# AT_long_bus.net
KiCad netlist of a schematic drawn in Altium Designer
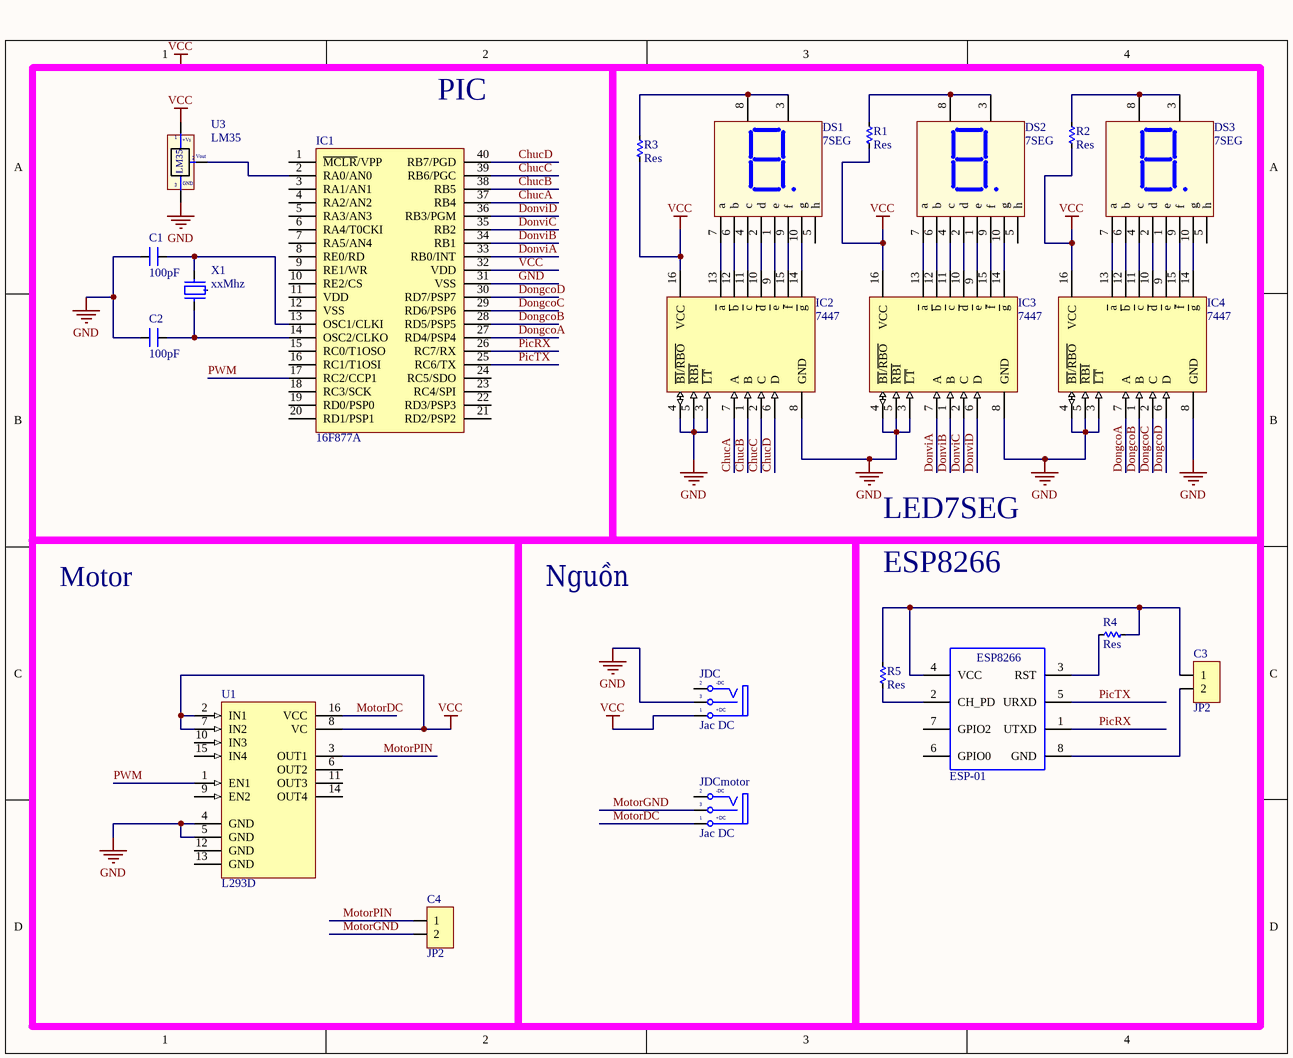
[diagram p0: AT long bus (13.3 x 4.2 inches).schdoc]

(export (version "E")
  (design (tool "Eeschema 10.0.6"))
  (components
    (comp (ref "C1")
      (value "100pF")
      (footprint "CN1")
      (description "Cap np  1pF - 472pF")
      (libsource (lib "syhaunguyen") (part "CN1"))
    )
    (comp (ref "C2")
      (value "100pF")
      (footprint "CN1")
      (description "Cap np  1pF - 472pF")
      (libsource (lib "syhaunguyen") (part "CN1"))
    )
    (comp (ref "C3")
      (value "JP2")
      (footprint "JP2-C1T")
      (description "WR-PHD 2.54 mm Angled Socket Header")
      (fields
        (field (name "MANUFACTURER") "Würth Elektronik eiSos GmbH")
        (field (name "PARTNO") "613002143121")
        (field (name "CREATED BY") "Karrer Zheng")
      )
      (libsource (lib "LIBRARY") (part "JP2"))
    )
    (comp (ref "C4")
      (value "JP2")
      (footprint "JP2-C1T")
      (description "WR-PHD 2.54 mm Angled Socket Header")
      (fields
        (field (name "MANUFACTURER") "Würth Elektronik eiSos GmbH")
        (field (name "PARTNO") "613002143121")
        (field (name "CREATED BY") "Karrer Zheng")
      )
      (libsource (lib "LIBRARY") (part "JP2"))
    )
    (comp (ref "DS1")
      (value "7SEG")
      (footprint "LED7SEG-1-0.56")
      (description "14.2 mm General Purpose Blue 7-Segment Display: CC, RH DP, Gray Surface")
      (fields (field (name "PUBLISHER") "Altium Limited"))
      (libsource (lib "LIBRARY") (part "LED7SEG-1"))
    )
    (comp (ref "DS2")
      (value "7SEG")
      (footprint "LED7SEG-1-0.56")
      (description "14.2 mm General Purpose Blue 7-Segment Display: CC, RH DP, Gray Surface")
      (fields (field (name "PUBLISHER") "Altium Limited"))
      (libsource (lib "LIBRARY") (part "LED7SEG-1"))
    )
    (comp (ref "DS3")
      (value "7SEG")
      (footprint "LED7SEG-1-0.56")
      (description "14.2 mm General Purpose Blue 7-Segment Display: CC, RH DP, Gray Surface")
      (fields (field (name "PUBLISHER") "Altium Limited"))
      (libsource (lib "LIBRARY") (part "LED7SEG-1"))
    )
    (comp (ref "IC1")
      (value "16F877A")
      (footprint "DIP40/W0.6")
      (description "8K FLASH, 368B RAM, 256B EFROM")
      (fields (field (name "COPYRIGHT BY") "VanDungEvn"))
      (libsource (lib "syhaunguyen") (part "16F877"))
    )
    (comp (ref "IC2")
      (value "7447")
      (footprint "DIP16/W0.3")
      (description "BCD to 7-Segment Decoder/Driver")
      (libsource (lib "syhaunguyen") (part "7447"))
    )
    (comp (ref "IC3")
      (value "7447")
      (footprint "DIP16/W0.3")
      (description "BCD to 7-Segment Decoder/Driver")
      (libsource (lib "syhaunguyen") (part "7447"))
    )
    (comp (ref "IC4")
      (value "7447")
      (footprint "DIP16/W0.3")
      (description "BCD to 7-Segment Decoder/Driver")
      (libsource (lib "syhaunguyen") (part "7447"))
    )
    (comp (ref "JDC")
      (value "Jac DC")
      (footprint "DC-IN")
      (description "Jac DC input")
      (libsource (lib "syhaunguyen") (part "DCIN"))
    )
    (comp (ref "JDCmotor")
      (value "Jac DC")
      (footprint "DC0")
      (description "Jac DC input")
      (libsource (lib "LIBRARY") (part "DCIN"))
    )
    (comp (ref "R1")
      (value "Res")
      (footprint "RES-1/2W")
      (fields
        (field (name "MANUFACTURER") "Generic Components")
        (field (name "PUBLISHER") "Altium Hobart Technology Centre")
      )
      (libsource (lib "LIBRARY") (part "Res"))
    )
    (comp (ref "R2")
      (value "Res")
      (footprint "RES-1/2W")
      (fields
        (field (name "MANUFACTURER") "Generic Components")
        (field (name "PUBLISHER") "Altium Hobart Technology Centre")
      )
      (libsource (lib "LIBRARY") (part "Res"))
    )
    (comp (ref "R3")
      (value "Res")
      (footprint "RES-1/2W")
      (fields
        (field (name "MANUFACTURER") "Generic Components")
        (field (name "PUBLISHER") "Altium Hobart Technology Centre")
      )
      (libsource (lib "LIBRARY") (part "Res"))
    )
    (comp (ref "R4")
      (value "Res")
      (footprint "RES-1/2W")
      (fields
        (field (name "MANUFACTURER") "Generic Components")
        (field (name "PUBLISHER") "Altium Hobart Technology Centre")
      )
      (libsource (lib "LIBRARY") (part "Res"))
    )
    (comp (ref "R5")
      (value "Res")
      (footprint "RES-1/2W")
      (fields
        (field (name "MANUFACTURER") "Generic Components")
        (field (name "PUBLISHER") "Altium Hobart Technology Centre")
      )
      (libsource (lib "LIBRARY") (part "Res"))
    )
    (comp (ref "U1")
      (value "L293D")
      (footprint "DIP16")
      (description "Push-Pull Four Channel Driver With Diode")
      (fields (field (name "PUBLISHER") "Altium Limited"))
      (libsource (lib "LIBRARY") (part "L293D"))
    )
    (comp (ref "U2")
      (value "ESP-01")
      (footprint "ESP8266")
      (description "ESP-12 Wi-Fi Module")
      (libsource (lib "LIBRARY") (part "ESP8266-01"))
    )
    (comp (ref "U3")
      (value "LM35")
      (footprint "TO92-123")
      (description "Teminal")
      (libsource (lib "LIBRARY") (part "LM35"))
    )
    (comp (ref "X1")
      (value "xxMhz")
      (footprint "XT3")
      (description "Crystal For all Crystal 2pin.")
      (libsource (lib "LIBRARY") (part "XT3"))
    )
  )
  (nets
    (net (code "1") (name "/ChucA") (class "Default")
      (node (ref "IC1") (pin "37") (pinfunction "RB4_37") (pintype "passive"))
      (node (ref "IC2") (pin "7") (pinfunction "A_7") (pintype "input"))
    )
    (net (code "2") (name "/ChucB") (class "Default")
      (node (ref "IC1") (pin "38") (pinfunction "RB5_38") (pintype "passive"))
      (node (ref "IC2") (pin "1") (pinfunction "B_1") (pintype "input"))
    )
    (net (code "3") (name "/ChucC") (class "Default")
      (node (ref "IC1") (pin "39") (pinfunction "RB6/PGC_39") (pintype "passive"))
      (node (ref "IC2") (pin "2") (pinfunction "C_2") (pintype "input"))
    )
    (net (code "4") (name "/ChucD") (class "Default")
      (node (ref "IC1") (pin "40") (pinfunction "RB7/PGD_40") (pintype "passive"))
      (node (ref "IC2") (pin "6") (pinfunction "D_6") (pintype "input"))
    )
    (net (code "5") (name "/DongcoA") (class "Default")
      (node (ref "IC1") (pin "27") (pinfunction "RD4/PSP4_27") (pintype "passive"))
      (node (ref "IC4") (pin "7") (pinfunction "A_7") (pintype "input"))
    )
    (net (code "6") (name "/DongcoB") (class "Default")
      (node (ref "IC1") (pin "28") (pinfunction "RD5/PSP5_28") (pintype "passive"))
      (node (ref "IC4") (pin "1") (pinfunction "B_1") (pintype "input"))
    )
    (net (code "7") (name "/DongcoC") (class "Default")
      (node (ref "IC1") (pin "29") (pinfunction "RD6/PSP6_29") (pintype "passive"))
      (node (ref "IC4") (pin "2") (pinfunction "C_2") (pintype "input"))
    )
    (net (code "8") (name "/DongcoD") (class "Default")
      (node (ref "IC1") (pin "30") (pinfunction "RD7/PSP7_30") (pintype "passive"))
      (node (ref "IC4") (pin "6") (pinfunction "D_6") (pintype "input"))
    )
    (net (code "9") (name "/DonviA") (class "Default")
      (node (ref "IC1") (pin "33") (pinfunction "RB0/INT_33") (pintype "passive"))
      (node (ref "IC3") (pin "7") (pinfunction "A_7") (pintype "input"))
    )
    (net (code "10") (name "/DonviB") (class "Default")
      (node (ref "IC1") (pin "34") (pinfunction "RB1_34") (pintype "passive"))
      (node (ref "IC3") (pin "1") (pinfunction "B_1") (pintype "input"))
    )
    (net (code "11") (name "/DonviC") (class "Default")
      (node (ref "IC1") (pin "35") (pinfunction "RB2_35") (pintype "passive"))
      (node (ref "IC3") (pin "2") (pinfunction "C_2") (pintype "input"))
    )
    (net (code "12") (name "/DonviD") (class "Default")
      (node (ref "IC1") (pin "36") (pinfunction "RB3/PGM_36") (pintype "passive"))
      (node (ref "IC3") (pin "6") (pinfunction "D_6") (pintype "input"))
    )
    (net (code "13") (name "/MotorDC") (class "Default")
      (node (ref "JDCmotor") (pin "1") (pinfunction "T_1") (pintype "passive"))
      (node (ref "U1") (pin "16") (pinfunction "VCC_16") (pintype "power_in"))
    )
    (net (code "14") (name "/MotorGND") (class "Default")
      (node (ref "C4") (pin "2") (pinfunction "2_2") (pintype "passive"))
      (node (ref "JDCmotor") (pin "3") (pinfunction "S_3") (pintype "power_in"))
    )
    (net (code "15") (name "/MotorPIN") (class "Default")
      (node (ref "C4") (pin "1") (pinfunction "1_1") (pintype "passive"))
      (node (ref "U1") (pin "3") (pinfunction "OUT1_3") (pintype "tri_state"))
    )
    (net (code "16") (name "/PWM") (class "Default")
      (node (ref "IC1") (pin "17") (pinfunction "RC2/CCP1_17") (pintype "passive"))
      (node (ref "U1") (pin "1") (pinfunction "EN1_1") (pintype "input"))
    )
    (net (code "17") (name "/PicRX") (class "Default")
      (node (ref "IC1") (pin "26") (pinfunction "RC7/RX_26") (pintype "passive"))
      (node (ref "U2") (pin "1") (pinfunction "UTXD_1") (pintype "passive"))
    )
    (net (code "18") (name "/PicTX") (class "Default")
      (node (ref "IC1") (pin "25") (pinfunction "RC6/TX_25") (pintype "passive"))
      (node (ref "U2") (pin "5") (pinfunction "URXD_5") (pintype "passive"))
    )
    (net (code "19") (name "GND") (class "Default")
      (node (ref "C1") (pin "1") (pinfunction "1_1") (pintype "passive"))
      (node (ref "C2") (pin "1") (pinfunction "1_1") (pintype "passive"))
      (node (ref "IC1") (pin "31") (pinfunction "VSS_31") (pintype "passive"))
      (node (ref "IC2") (pin "3") (pinfunction "~{LT}_3") (pintype "input"))
      (node (ref "IC2") (pin "4") (pinfunction "~{BI}/~{RBO}_4") (pintype "bidirectional"))
      (node (ref "IC2") (pin "5") (pinfunction "~{RBI}_5") (pintype "input"))
      (node (ref "IC2") (pin "8") (pinfunction "GND_8") (pintype "power_in"))
      (node (ref "IC3") (pin "3") (pinfunction "~{LT}_3") (pintype "input"))
      (node (ref "IC3") (pin "4") (pinfunction "~{BI}/~{RBO}_4") (pintype "bidirectional"))
      (node (ref "IC3") (pin "5") (pinfunction "~{RBI}_5") (pintype "input"))
      (node (ref "IC3") (pin "8") (pinfunction "GND_8") (pintype "power_in"))
      (node (ref "IC4") (pin "3") (pinfunction "~{LT}_3") (pintype "input"))
      (node (ref "IC4") (pin "4") (pinfunction "~{BI}/~{RBO}_4") (pintype "bidirectional"))
      (node (ref "IC4") (pin "5") (pinfunction "~{RBI}_5") (pintype "input"))
      (node (ref "IC4") (pin "8") (pinfunction "GND_8") (pintype "power_in"))
      (node (ref "JDC") (pin "3") (pinfunction "S_3") (pintype "power_in"))
      (node (ref "U1") (pin "4") (pinfunction "GND_4") (pintype "power_in"))
      (node (ref "U1") (pin "5") (pinfunction "GND_5") (pintype "power_in"))
      (node (ref "U3") (pin "3") (pinfunction "-_3") (pintype "passive"))
    )
    (net (code "20") (name "Net-(DS1-Vcc-Pad3)") (class "Default")
      (node (ref "DS1") (pin "3") (pinfunction "Vcc_3") (pintype "passive"))
      (node (ref "DS1") (pin "8") (pinfunction "Vcc_8") (pintype "passive"))
      (node (ref "R3") (pin "1") (pinfunction "1_1") (pintype "passive"))
    )
    (net (code "21") (name "Net-(DS1-a)") (class "Default")
      (node (ref "DS1") (pin "7") (pinfunction "a_7") (pintype "passive"))
      (node (ref "IC2") (pin "13") (pinfunction "~{a}_13") (pintype "open_collector"))
    )
    (net (code "22") (name "Net-(DS1-b)") (class "Default")
      (node (ref "DS1") (pin "6") (pinfunction "b_6") (pintype "passive"))
      (node (ref "IC2") (pin "12") (pinfunction "~{b}_12") (pintype "open_collector"))
    )
    (net (code "23") (name "Net-(DS1-c)") (class "Default")
      (node (ref "DS1") (pin "4") (pinfunction "c_4") (pintype "passive"))
      (node (ref "IC2") (pin "11") (pinfunction "~{c}_11") (pintype "open_collector"))
    )
    (net (code "24") (name "Net-(DS1-d)") (class "Default")
      (node (ref "DS1") (pin "2") (pinfunction "d_2") (pintype "passive"))
      (node (ref "IC2") (pin "10") (pinfunction "~{d}_10") (pintype "open_collector"))
    )
    (net (code "25") (name "Net-(DS1-e)") (class "Default")
      (node (ref "DS1") (pin "1") (pinfunction "e_1") (pintype "passive"))
      (node (ref "IC2") (pin "9") (pinfunction "~{e}_9") (pintype "open_collector"))
    )
    (net (code "26") (name "Net-(DS1-f)") (class "Default")
      (node (ref "DS1") (pin "9") (pinfunction "f_9") (pintype "passive"))
      (node (ref "IC2") (pin "15") (pinfunction "~{f}_15") (pintype "open_collector"))
    )
    (net (code "27") (name "Net-(DS1-g)") (class "Default")
      (node (ref "DS1") (pin "10") (pinfunction "g_10") (pintype "passive"))
      (node (ref "IC2") (pin "14") (pinfunction "~{g}_14") (pintype "open_collector"))
    )
    (net (code "28") (name "Net-(DS2-Vcc-Pad3)") (class "Default")
      (node (ref "DS2") (pin "3") (pinfunction "Vcc_3") (pintype "passive"))
      (node (ref "DS2") (pin "8") (pinfunction "Vcc_8") (pintype "passive"))
      (node (ref "R1") (pin "1") (pinfunction "1_1") (pintype "passive"))
    )
    (net (code "29") (name "Net-(DS2-a)") (class "Default")
      (node (ref "DS2") (pin "7") (pinfunction "a_7") (pintype "passive"))
      (node (ref "IC3") (pin "13") (pinfunction "~{a}_13") (pintype "open_collector"))
    )
    (net (code "30") (name "Net-(DS2-b)") (class "Default")
      (node (ref "DS2") (pin "6") (pinfunction "b_6") (pintype "passive"))
      (node (ref "IC3") (pin "12") (pinfunction "~{b}_12") (pintype "open_collector"))
    )
    (net (code "31") (name "Net-(DS2-c)") (class "Default")
      (node (ref "DS2") (pin "4") (pinfunction "c_4") (pintype "passive"))
      (node (ref "IC3") (pin "11") (pinfunction "~{c}_11") (pintype "open_collector"))
    )
    (net (code "32") (name "Net-(DS2-d)") (class "Default")
      (node (ref "DS2") (pin "2") (pinfunction "d_2") (pintype "passive"))
      (node (ref "IC3") (pin "10") (pinfunction "~{d}_10") (pintype "open_collector"))
    )
    (net (code "33") (name "Net-(DS2-e)") (class "Default")
      (node (ref "DS2") (pin "1") (pinfunction "e_1") (pintype "passive"))
      (node (ref "IC3") (pin "9") (pinfunction "~{e}_9") (pintype "open_collector"))
    )
    (net (code "34") (name "Net-(DS2-f)") (class "Default")
      (node (ref "DS2") (pin "9") (pinfunction "f_9") (pintype "passive"))
      (node (ref "IC3") (pin "15") (pinfunction "~{f}_15") (pintype "open_collector"))
    )
    (net (code "35") (name "Net-(DS2-g)") (class "Default")
      (node (ref "DS2") (pin "10") (pinfunction "g_10") (pintype "passive"))
      (node (ref "IC3") (pin "14") (pinfunction "~{g}_14") (pintype "open_collector"))
    )
    (net (code "36") (name "Net-(DS3-Vcc-Pad3)") (class "Default")
      (node (ref "DS3") (pin "3") (pinfunction "Vcc_3") (pintype "passive"))
      (node (ref "DS3") (pin "8") (pinfunction "Vcc_8") (pintype "passive"))
      (node (ref "R2") (pin "1") (pinfunction "1_1") (pintype "passive"))
    )
    (net (code "37") (name "Net-(DS3-a)") (class "Default")
      (node (ref "DS3") (pin "7") (pinfunction "a_7") (pintype "passive"))
      (node (ref "IC4") (pin "13") (pinfunction "~{a}_13") (pintype "open_collector"))
    )
    (net (code "38") (name "Net-(DS3-b)") (class "Default")
      (node (ref "DS3") (pin "6") (pinfunction "b_6") (pintype "passive"))
      (node (ref "IC4") (pin "12") (pinfunction "~{b}_12") (pintype "open_collector"))
    )
    (net (code "39") (name "Net-(DS3-c)") (class "Default")
      (node (ref "DS3") (pin "4") (pinfunction "c_4") (pintype "passive"))
      (node (ref "IC4") (pin "11") (pinfunction "~{c}_11") (pintype "open_collector"))
    )
    (net (code "40") (name "Net-(DS3-d)") (class "Default")
      (node (ref "DS3") (pin "2") (pinfunction "d_2") (pintype "passive"))
      (node (ref "IC4") (pin "10") (pinfunction "~{d}_10") (pintype "open_collector"))
    )
    (net (code "41") (name "Net-(DS3-e)") (class "Default")
      (node (ref "DS3") (pin "1") (pinfunction "e_1") (pintype "passive"))
      (node (ref "IC4") (pin "9") (pinfunction "~{e}_9") (pintype "open_collector"))
    )
    (net (code "42") (name "Net-(DS3-f)") (class "Default")
      (node (ref "DS3") (pin "9") (pinfunction "f_9") (pintype "passive"))
      (node (ref "IC4") (pin "15") (pinfunction "~{f}_15") (pintype "open_collector"))
    )
    (net (code "43") (name "Net-(DS3-g)") (class "Default")
      (node (ref "DS3") (pin "10") (pinfunction "g_10") (pintype "passive"))
      (node (ref "IC4") (pin "14") (pinfunction "~{g}_14") (pintype "open_collector"))
    )
    (net (code "44") (name "Net-(IC1-OSC1{slash}CLKI)") (class "Default")
      (node (ref "C1") (pin "2") (pinfunction "2_2") (pintype "passive"))
      (node (ref "IC1") (pin "13") (pinfunction "OSC1/CLKI_13") (pintype "passive"))
      (node (ref "X1") (pin "2") (pinfunction "2_2") (pintype "passive"))
    )
    (net (code "45") (name "Net-(IC1-OSC2{slash}CLKO)") (class "Default")
      (node (ref "C2") (pin "2") (pinfunction "2_2") (pintype "passive"))
      (node (ref "IC1") (pin "14") (pinfunction "OSC2/CLKO_14") (pintype "passive"))
      (node (ref "X1") (pin "1") (pinfunction "1_1") (pintype "passive"))
    )
    (net (code "46") (name "Net-(IC1-RA0{slash}AN0)") (class "Default")
      (node (ref "IC1") (pin "2") (pinfunction "RA0/AN0_2") (pintype "passive"))
      (node (ref "U3") (pin "2") (pinfunction "Vout_2") (pintype "passive"))
    )
    (net (code "47") (name "Net-(U2-CH_PD)") (class "Default")
      (node (ref "R5") (pin "2") (pinfunction "2_2") (pintype "passive"))
      (node (ref "U2") (pin "2") (pinfunction "CH_PD_2") (pintype "passive"))
    )
    (net (code "48") (name "Net-(U2-GND)") (class "Default")
      (node (ref "C3") (pin "2") (pinfunction "2_2") (pintype "passive"))
      (node (ref "U2") (pin "8") (pinfunction "GND_8") (pintype "passive"))
    )
    (net (code "49") (name "Net-(U2-RST)") (class "Default")
      (node (ref "R4") (pin "2") (pinfunction "2_2") (pintype "passive"))
      (node (ref "U2") (pin "3") (pinfunction "RST_3") (pintype "passive"))
    )
    (net (code "50") (name "Net-(U2-VCC)") (class "Default")
      (node (ref "C3") (pin "1") (pinfunction "1_1") (pintype "passive"))
      (node (ref "R4") (pin "1") (pinfunction "1_1") (pintype "passive"))
      (node (ref "R5") (pin "1") (pinfunction "1_1") (pintype "passive"))
      (node (ref "U2") (pin "4") (pinfunction "VCC_4") (pintype "passive"))
    )
    (net (code "51") (name "VCC") (class "Default")
      (node (ref "IC1") (pin "32") (pinfunction "VDD_32") (pintype "passive"))
      (node (ref "IC2") (pin "16") (pinfunction "VCC_16") (pintype "power_in"))
      (node (ref "IC3") (pin "16") (pinfunction "VCC_16") (pintype "power_in"))
      (node (ref "IC4") (pin "16") (pinfunction "VCC_16") (pintype "power_in"))
      (node (ref "JDC") (pin "1") (pinfunction "T_1") (pintype "passive"))
      (node (ref "R1") (pin "2") (pinfunction "2_2") (pintype "passive"))
      (node (ref "R2") (pin "2") (pinfunction "2_2") (pintype "passive"))
      (node (ref "R3") (pin "2") (pinfunction "2_2") (pintype "passive"))
      (node (ref "U1") (pin "2") (pinfunction "IN1_2") (pintype "input"))
      (node (ref "U1") (pin "7") (pinfunction "IN2_7") (pintype "input"))
      (node (ref "U1") (pin "8") (pinfunction "VC_8") (pintype "power_in"))
      (node (ref "U3") (pin "1") (pinfunction "+Vs_1") (pintype "passive"))
    )
    (net (code "52") (name "unconnected-(DS1-h-Pad5)") (class "Default")
      (node (ref "DS1") (pin "5") (pinfunction "h_5") (pintype "passive"))
    )
    (net (code "53") (name "unconnected-(DS2-h-Pad5)") (class "Default")
      (node (ref "DS2") (pin "5") (pinfunction "h_5") (pintype "passive"))
    )
    (net (code "54") (name "unconnected-(DS3-h-Pad5)") (class "Default")
      (node (ref "DS3") (pin "5") (pinfunction "h_5") (pintype "passive"))
    )
    (net (code "55") (name "unconnected-(IC1-RA1{slash}AN1-Pad3)") (class "Default")
      (node (ref "IC1") (pin "3") (pinfunction "RA1/AN1_3") (pintype "passive"))
    )
    (net (code "56") (name "unconnected-(IC1-RA2{slash}AN2-Pad4)") (class "Default")
      (node (ref "IC1") (pin "4") (pinfunction "RA2/AN2_4") (pintype "passive"))
    )
    (net (code "57") (name "unconnected-(IC1-RA3{slash}AN3-Pad5)") (class "Default")
      (node (ref "IC1") (pin "5") (pinfunction "RA3/AN3_5") (pintype "passive"))
    )
    (net (code "58") (name "unconnected-(IC1-RA4{slash}T0CKI-Pad6)") (class "Default")
      (node (ref "IC1") (pin "6") (pinfunction "RA4/T0CKI_6") (pintype "passive"))
    )
    (net (code "59") (name "unconnected-(IC1-RA5{slash}AN4-Pad7)") (class "Default")
      (node (ref "IC1") (pin "7") (pinfunction "RA5/AN4_7") (pintype "passive"))
    )
    (net (code "60") (name "unconnected-(IC1-RC0{slash}T1OSO-Pad15)") (class "Default")
      (node (ref "IC1") (pin "15") (pinfunction "RC0/T1OSO_15") (pintype "passive"))
    )
    (net (code "61") (name "unconnected-(IC1-RC1{slash}T1OSI-Pad16)") (class "Default")
      (node (ref "IC1") (pin "16") (pinfunction "RC1/T1OSI_16") (pintype "passive"))
    )
    (net (code "62") (name "unconnected-(IC1-RC3{slash}SCK-Pad18)") (class "Default")
      (node (ref "IC1") (pin "18") (pinfunction "RC3/SCK_18") (pintype "passive"))
    )
    (net (code "63") (name "unconnected-(IC1-RC4{slash}SPI-Pad23)") (class "Default")
      (node (ref "IC1") (pin "23") (pinfunction "RC4/SPI_23") (pintype "passive"))
    )
    (net (code "64") (name "unconnected-(IC1-RC5{slash}SDO-Pad24)") (class "Default")
      (node (ref "IC1") (pin "24") (pinfunction "RC5/SDO_24") (pintype "passive"))
    )
    (net (code "65") (name "unconnected-(IC1-RD0{slash}PSP0-Pad19)") (class "Default")
      (node (ref "IC1") (pin "19") (pinfunction "RD0/PSP0_19") (pintype "passive"))
    )
    (net (code "66") (name "unconnected-(IC1-RD1{slash}PSP1-Pad20)") (class "Default")
      (node (ref "IC1") (pin "20") (pinfunction "RD1/PSP1_20") (pintype "passive"))
    )
    (net (code "67") (name "unconnected-(IC1-RD2{slash}PSP2-Pad21)") (class "Default")
      (node (ref "IC1") (pin "21") (pinfunction "RD2/PSP2_21") (pintype "passive"))
    )
    (net (code "68") (name "unconnected-(IC1-RD3{slash}PSP3-Pad22)") (class "Default")
      (node (ref "IC1") (pin "22") (pinfunction "RD3/PSP3_22") (pintype "passive"))
    )
    (net (code "69") (name "unconnected-(IC1-RE0{slash}RD-Pad8)") (class "Default")
      (node (ref "IC1") (pin "8") (pinfunction "RE0/RD_8") (pintype "passive"))
    )
    (net (code "70") (name "unconnected-(IC1-RE1{slash}WR-Pad9)") (class "Default")
      (node (ref "IC1") (pin "9") (pinfunction "RE1/WR_9") (pintype "passive"))
    )
    (net (code "71") (name "unconnected-(IC1-RE2{slash}CS-Pad10)") (class "Default")
      (node (ref "IC1") (pin "10") (pinfunction "RE2/CS_10") (pintype "passive"))
    )
    (net (code "72") (name "unconnected-(IC1-VDD-Pad11)") (class "Default")
      (node (ref "IC1") (pin "11") (pinfunction "VDD_11") (pintype "passive"))
    )
    (net (code "73") (name "unconnected-(IC1-VSS-Pad12)") (class "Default")
      (node (ref "IC1") (pin "12") (pinfunction "VSS_12") (pintype "passive"))
    )
    (net (code "74") (name "unconnected-(IC1-~{MCLR}{slash}VPP-Pad1)") (class "Default")
      (node (ref "IC1") (pin "1") (pinfunction "~{MCLR}/VPP_1") (pintype "passive"))
    )
    (net (code "75") (name "unconnected-(JDC-TN-Pad2)") (class "Default")
      (node (ref "JDC") (pin "2") (pinfunction "TN_2") (pintype "passive"))
    )
    (net (code "76") (name "unconnected-(JDCmotor-TN-Pad2)") (class "Default")
      (node (ref "JDCmotor") (pin "2") (pinfunction "TN_2") (pintype "passive"))
    )
    (net (code "77") (name "unconnected-(U1-EN2-Pad9)") (class "Default")
      (node (ref "U1") (pin "9") (pinfunction "EN2_9") (pintype "input"))
    )
    (net (code "78") (name "unconnected-(U1-GND-Pad12)") (class "Default")
      (node (ref "U1") (pin "12") (pinfunction "GND_12") (pintype "power_in"))
    )
    (net (code "79") (name "unconnected-(U1-GND-Pad13)") (class "Default")
      (node (ref "U1") (pin "13") (pinfunction "GND_13") (pintype "power_in"))
    )
    (net (code "80") (name "unconnected-(U1-IN3-Pad10)") (class "Default")
      (node (ref "U1") (pin "10") (pinfunction "IN3_10") (pintype "input"))
    )
    (net (code "81") (name "unconnected-(U1-IN4-Pad15)") (class "Default")
      (node (ref "U1") (pin "15") (pinfunction "IN4_15") (pintype "input"))
    )
    (net (code "82") (name "unconnected-(U1-OUT2-Pad6)") (class "Default")
      (node (ref "U1") (pin "6") (pinfunction "OUT2_6") (pintype "tri_state"))
    )
    (net (code "83") (name "unconnected-(U1-OUT3-Pad11)") (class "Default")
      (node (ref "U1") (pin "11") (pinfunction "OUT3_11") (pintype "tri_state"))
    )
    (net (code "84") (name "unconnected-(U1-OUT4-Pad14)") (class "Default")
      (node (ref "U1") (pin "14") (pinfunction "OUT4_14") (pintype "tri_state"))
    )
    (net (code "85") (name "unconnected-(U2-GPIO0-Pad6)") (class "Default")
      (node (ref "U2") (pin "6") (pinfunction "GPIO0_6") (pintype "passive"))
    )
    (net (code "86") (name "unconnected-(U2-GPIO2-Pad7)") (class "Default")
      (node (ref "U2") (pin "7") (pinfunction "GPIO2_7") (pintype "passive"))
    )
    (net (code "87") (name "unconnected-(X1-Pad3)") (class "Default")
      (node (ref "X1") (pin "3") (pinfunction "3_3") (pintype "passive"))
    )
  )
)
